# Backplane.net
KiCad netlist of a schematic drawn in EAGLE
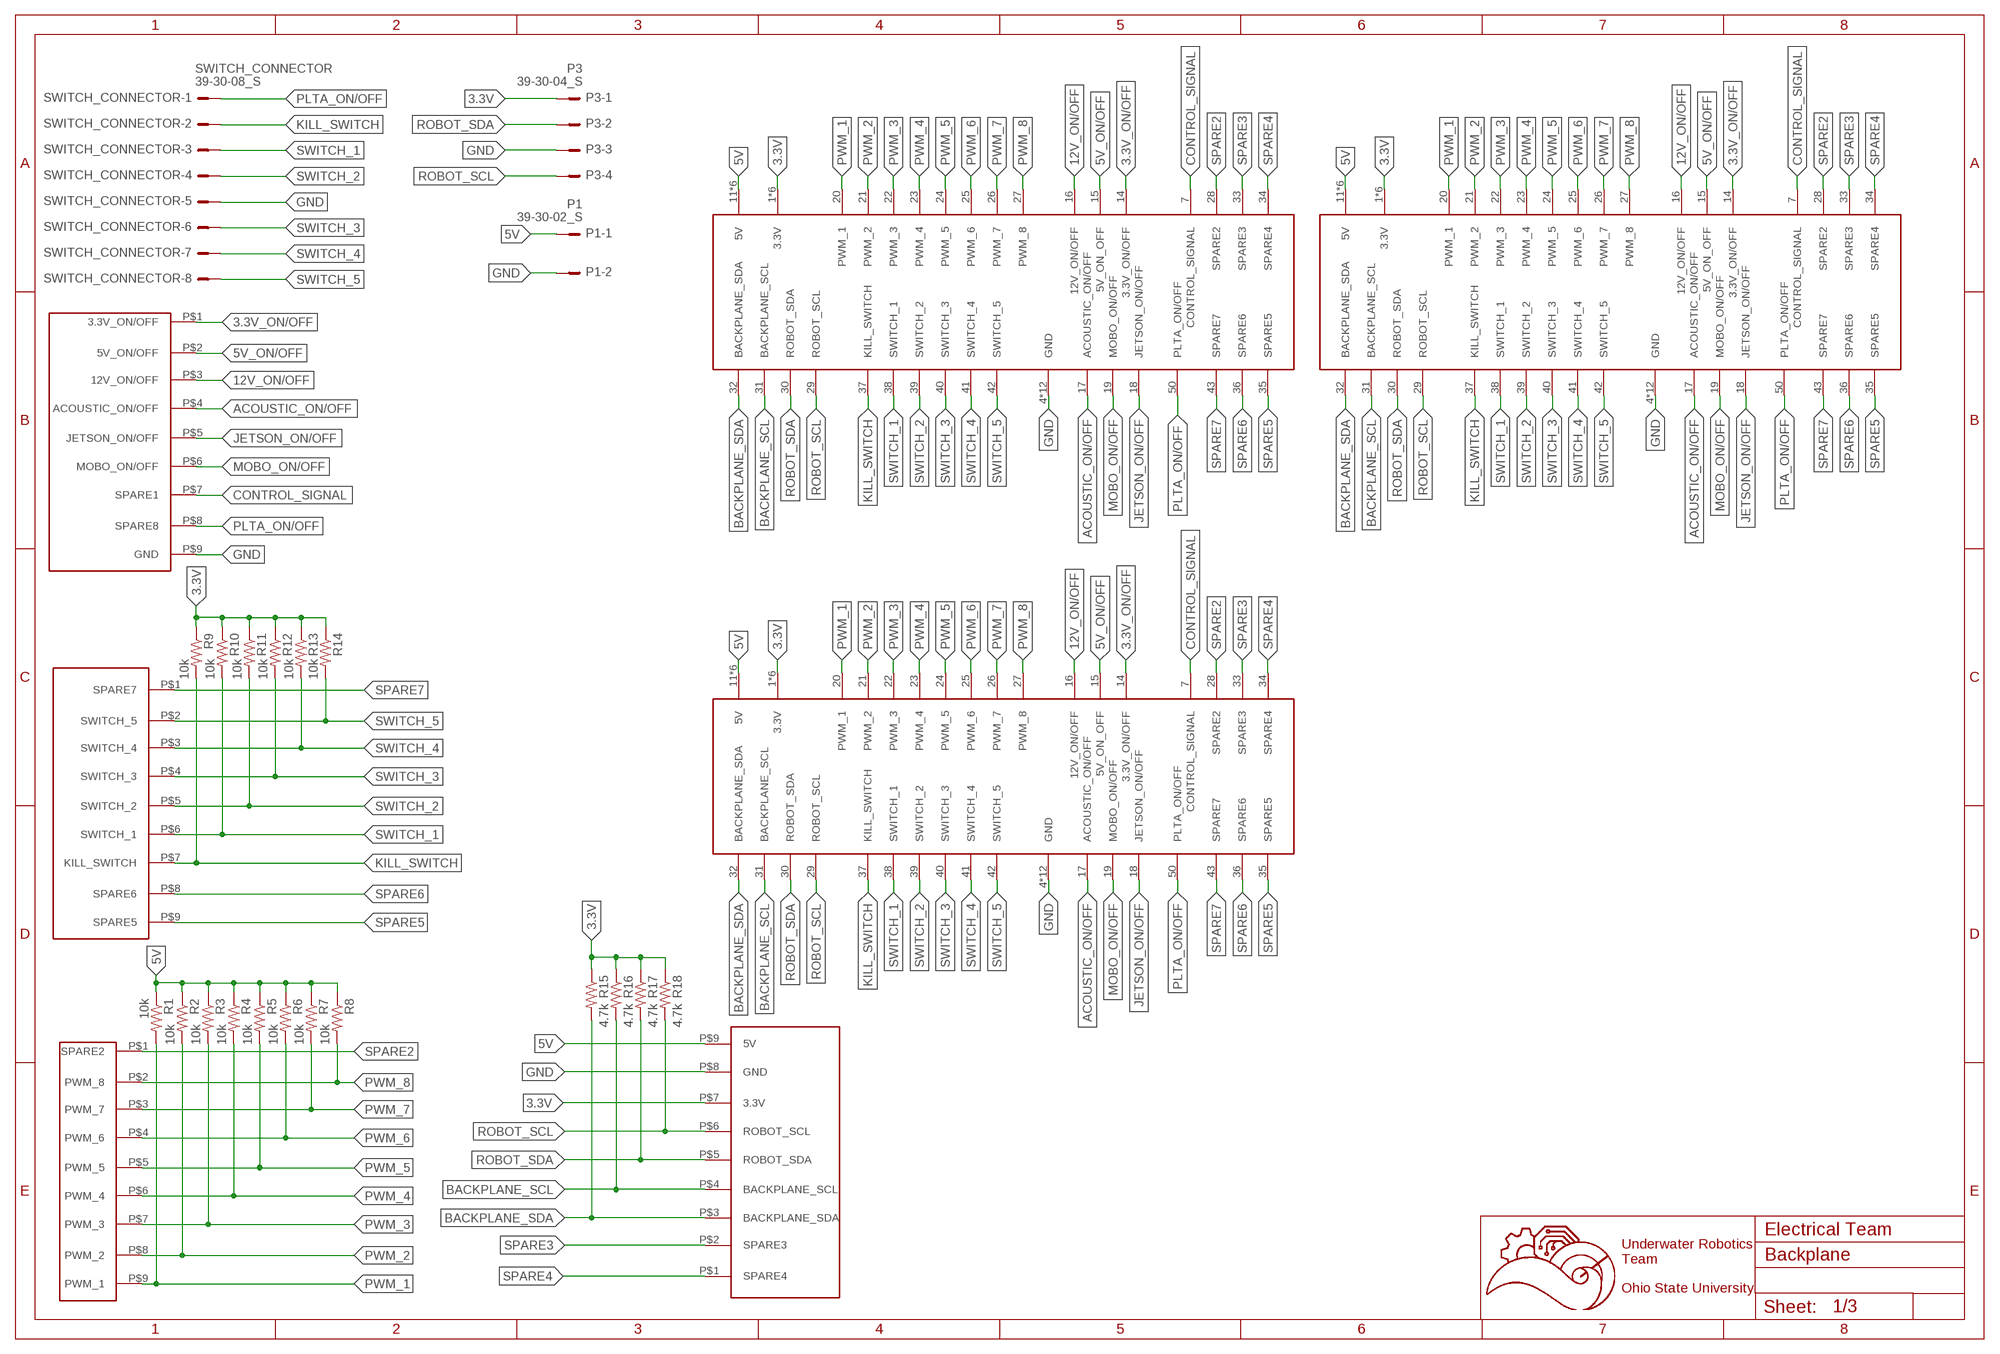
[diagram p0: schematic, sheet 1]
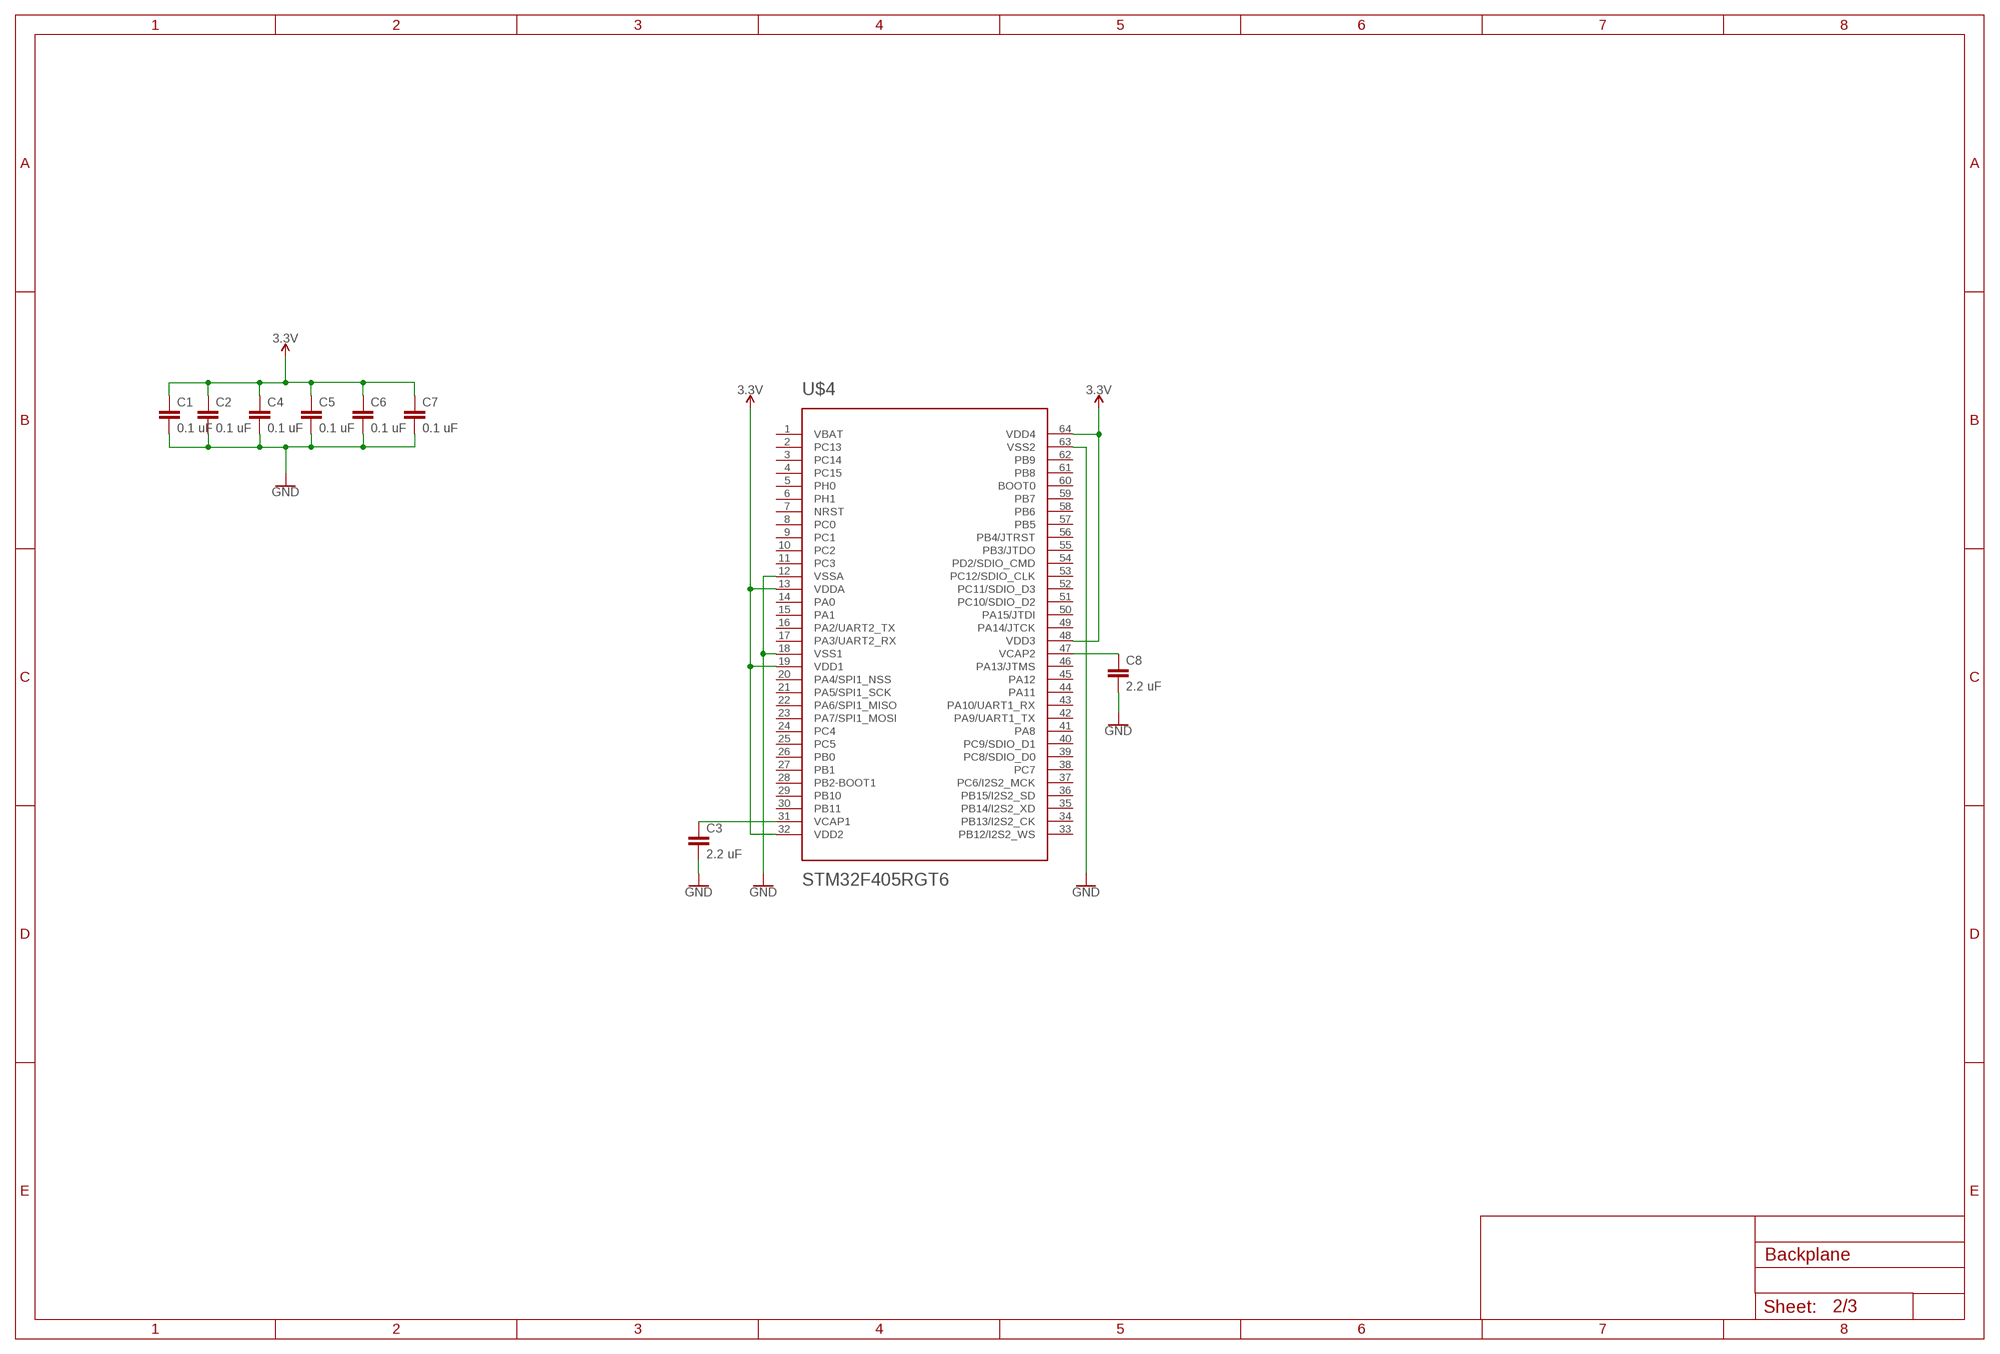
[diagram p1: schematic, sheet 2]

(export (version "E")
  (design (tool "Eeschema 10.0.6"))
  (components
    (comp (ref "C1")
      (value "0.1 uF")
      (footprint "eagle-import:C0603")
      (libsource (lib "eagle-import") (part "C-EUC0603"))
    )
    (comp (ref "C2")
      (value "0.1 uF")
      (footprint "eagle-import:C0603")
      (libsource (lib "eagle-import") (part "C-EUC0603"))
    )
    (comp (ref "C3")
      (value "2.2 uF")
      (footprint "eagle-import:C0603")
      (libsource (lib "eagle-import") (part "C-EUC0603"))
    )
    (comp (ref "C4")
      (value "0.1 uF")
      (footprint "eagle-import:C0603")
      (libsource (lib "eagle-import") (part "C-EUC0603"))
    )
    (comp (ref "C5")
      (value "0.1 uF")
      (footprint "eagle-import:C0603")
      (libsource (lib "eagle-import") (part "C-EUC0603"))
    )
    (comp (ref "C6")
      (value "0.1 uF")
      (footprint "eagle-import:C0603")
      (libsource (lib "eagle-import") (part "C-EUC0603"))
    )
    (comp (ref "C7")
      (value "0.1 uF")
      (footprint "eagle-import:C0603")
      (libsource (lib "eagle-import") (part "C-EUC0603"))
    )
    (comp (ref "C8")
      (value "2.2 uF")
      (footprint "eagle-import:C0603")
      (libsource (lib "eagle-import") (part "C-EUC0603"))
    )
    (comp (ref "U$4")
      (value "STM32F405RGT6")
      (footprint "eagle-import:TQFP64")
      (libsource (lib "eagle-import") (part "STM32F405RG"))
    )
    (comp (ref "P1")
      (value "39-30-02_S")
      (footprint "eagle-import:39-30-_02_")
      (libsource (lib "eagle-import") (part "39-30-?02?_S"))
    )
    (comp (ref "P3")
      (value "39-30-04_S")
      (footprint "eagle-import:39-30-_04_")
      (libsource (lib "eagle-import") (part "39-30-?04?_S"))
    )
    (comp (ref "R1")
      (value "10k")
      (footprint "eagle-import:R0603")
      (libsource (lib "eagle-import") (part "R-US_R0603"))
    )
    (comp (ref "R2")
      (value "10k")
      (footprint "eagle-import:R0603")
      (libsource (lib "eagle-import") (part "R-US_R0603"))
    )
    (comp (ref "R3")
      (value "10k")
      (footprint "eagle-import:R0603")
      (libsource (lib "eagle-import") (part "R-US_R0603"))
    )
    (comp (ref "R4")
      (value "10k")
      (footprint "eagle-import:R0603")
      (libsource (lib "eagle-import") (part "R-US_R0603"))
    )
    (comp (ref "R5")
      (value "10k")
      (footprint "eagle-import:R0603")
      (libsource (lib "eagle-import") (part "R-US_R0603"))
    )
    (comp (ref "R6")
      (value "10k")
      (footprint "eagle-import:R0603")
      (libsource (lib "eagle-import") (part "R-US_R0603"))
    )
    (comp (ref "R7")
      (value "10k")
      (footprint "eagle-import:R0603")
      (libsource (lib "eagle-import") (part "R-US_R0603"))
    )
    (comp (ref "R8")
      (value "10k")
      (footprint "eagle-import:R0603")
      (libsource (lib "eagle-import") (part "R-US_R0603"))
    )
    (comp (ref "R9")
      (value "10k")
      (footprint "eagle-import:R0603")
      (libsource (lib "eagle-import") (part "R-US_R0603"))
    )
    (comp (ref "R10")
      (value "10k")
      (footprint "eagle-import:R0603")
      (libsource (lib "eagle-import") (part "R-US_R0603"))
    )
    (comp (ref "R11")
      (value "10k")
      (footprint "eagle-import:R0603")
      (libsource (lib "eagle-import") (part "R-US_R0603"))
    )
    (comp (ref "R12")
      (value "10k")
      (footprint "eagle-import:R0603")
      (libsource (lib "eagle-import") (part "R-US_R0603"))
    )
    (comp (ref "R13")
      (value "10k")
      (footprint "eagle-import:R0603")
      (libsource (lib "eagle-import") (part "R-US_R0603"))
    )
    (comp (ref "R14")
      (value "10k")
      (footprint "eagle-import:R0603")
      (libsource (lib "eagle-import") (part "R-US_R0603"))
    )
    (comp (ref "R15")
      (value "4.7k")
      (footprint "eagle-import:R0603")
      (libsource (lib "eagle-import") (part "R-US_R0603"))
    )
    (comp (ref "R16")
      (value "4.7k")
      (footprint "eagle-import:R0603")
      (libsource (lib "eagle-import") (part "R-US_R0603"))
    )
    (comp (ref "R17")
      (value "4.7k")
      (footprint "eagle-import:R0603")
      (libsource (lib "eagle-import") (part "R-US_R0603"))
    )
    (comp (ref "R18")
      (value "4.7k")
      (footprint "eagle-import:R0603")
      (libsource (lib "eagle-import") (part "R-US_R0603"))
    )
    (comp (ref "SWITCH_CONNECTOR")
      (value "39-30-08_S")
      (footprint "eagle-import:39-30-_08_")
      (libsource (lib "eagle-import") (part "39-30-?08?_S"))
    )
    (comp (ref "U$1")
      (value "5530843-FEMALE")
      (footprint "eagle-import:5530843-6-BACKPLANEMATE")
      (libsource (lib "eagle-import") (part "5530843-FEMALE"))
    )
    (comp (ref "U$2")
      (value "5530843-FEMALE")
      (footprint "eagle-import:5530843-6-BACKPLANEMATE")
      (libsource (lib "eagle-import") (part "5530843-FEMALE"))
    )
    (comp (ref "U$3")
      (value "5530843-FEMALE")
      (footprint "eagle-import:5530843-6-BACKPLANEMATE")
      (libsource (lib "eagle-import") (part "5530843-FEMALE"))
    )
    (comp (ref "U$5")
      (value "929870-01-09_1")
      (footprint "eagle-import:929852-01-09_1ROW")
      (libsource (lib "eagle-import") (part "929870-01-09_1"))
    )
    (comp (ref "U$6")
      (value "929870-01-09_2")
      (footprint "eagle-import:929852-01-09_1ROW")
      (libsource (lib "eagle-import") (part "929870-01-09_2"))
    )
    (comp (ref "U$7")
      (value "929870-01-09_3")
      (footprint "eagle-import:929852-01-09_1ROW")
      (libsource (lib "eagle-import") (part "929870-01-09_3"))
    )
    (comp (ref "U$8")
      (value "929870-01-09_4")
      (footprint "eagle-import:929852-01-09_1ROW")
      (libsource (lib "eagle-import") (part "929870-01-09_4"))
    )
  )
  (nets
    (net (code "1") (name "3.3V") (class "Default")
      (node (ref "C1") (pin "1") (pinfunction "1_1") (pintype "passive"))
      (node (ref "C2") (pin "1") (pinfunction "1_1") (pintype "passive"))
      (node (ref "C4") (pin "1") (pinfunction "1_1") (pintype "passive"))
      (node (ref "C5") (pin "1") (pinfunction "1_1") (pintype "passive"))
      (node (ref "C6") (pin "1") (pinfunction "1_1") (pintype "passive"))
      (node (ref "C7") (pin "1") (pinfunction "1_1") (pintype "passive"))
      (node (ref "P3") (pin "1") (pinfunction "P_1") (pintype "passive"))
      (node (ref "R10") (pin "1") (pinfunction "1_1") (pintype "passive"))
      (node (ref "R11") (pin "1") (pinfunction "1_1") (pintype "passive"))
      (node (ref "R12") (pin "1") (pinfunction "1_1") (pintype "passive"))
      (node (ref "R13") (pin "1") (pinfunction "1_1") (pintype "passive"))
      (node (ref "R14") (pin "1") (pinfunction "1_1") (pintype "passive"))
      (node (ref "R15") (pin "1") (pinfunction "1_1") (pintype "passive"))
      (node (ref "R16") (pin "1") (pinfunction "1_1") (pintype "passive"))
      (node (ref "R17") (pin "1") (pinfunction "1_1") (pintype "passive"))
      (node (ref "R18") (pin "1") (pinfunction "1_1") (pintype "passive"))
      (node (ref "R9") (pin "1") (pinfunction "1_1") (pintype "passive"))
      (node (ref "U$1") (pin "1") (pinfunction "3.3V_1") (pintype "bidirectional"))
      (node (ref "U$1") (pin "2") (pinfunction "3.3V_2") (pintype "bidirectional"))
      (node (ref "U$1") (pin "3") (pinfunction "3.3V_3") (pintype "bidirectional"))
      (node (ref "U$1") (pin "54") (pinfunction "3.3V_54") (pintype "bidirectional"))
      (node (ref "U$1") (pin "55") (pinfunction "3.3V_55") (pintype "bidirectional"))
      (node (ref "U$1") (pin "56") (pinfunction "3.3V_56") (pintype "bidirectional"))
      (node (ref "U$2") (pin "1") (pinfunction "3.3V_1") (pintype "bidirectional"))
      (node (ref "U$2") (pin "2") (pinfunction "3.3V_2") (pintype "bidirectional"))
      (node (ref "U$2") (pin "3") (pinfunction "3.3V_3") (pintype "bidirectional"))
      (node (ref "U$2") (pin "54") (pinfunction "3.3V_54") (pintype "bidirectional"))
      (node (ref "U$2") (pin "55") (pinfunction "3.3V_55") (pintype "bidirectional"))
      (node (ref "U$2") (pin "56") (pinfunction "3.3V_56") (pintype "bidirectional"))
      (node (ref "U$3") (pin "1") (pinfunction "3.3V_1") (pintype "bidirectional"))
      (node (ref "U$3") (pin "2") (pinfunction "3.3V_2") (pintype "bidirectional"))
      (node (ref "U$3") (pin "3") (pinfunction "3.3V_3") (pintype "bidirectional"))
      (node (ref "U$3") (pin "54") (pinfunction "3.3V_54") (pintype "bidirectional"))
      (node (ref "U$3") (pin "55") (pinfunction "3.3V_55") (pintype "bidirectional"))
      (node (ref "U$3") (pin "56") (pinfunction "3.3V_56") (pintype "bidirectional"))
      (node (ref "U$4") (pin "13") (pinfunction "VDDA_13") (pintype "bidirectional"))
      (node (ref "U$4") (pin "19") (pinfunction "VDD1_19") (pintype "bidirectional"))
      (node (ref "U$4") (pin "32") (pinfunction "VDD2_32") (pintype "bidirectional"))
      (node (ref "U$4") (pin "48") (pinfunction "VDD3_48") (pintype "bidirectional"))
      (node (ref "U$4") (pin "64") (pinfunction "VDD4_64") (pintype "bidirectional"))
      (node (ref "U$8") (pin "P$7") (pinfunction "3.3V_P$7") (pintype "bidirectional"))
    )
    (net (code "2") (name "3.3V_ON{slash}OFF") (class "Default")
      (node (ref "U$1") (pin "14") (pinfunction "3.3V_ON/OFF_14") (pintype "bidirectional"))
      (node (ref "U$2") (pin "14") (pinfunction "3.3V_ON/OFF_14") (pintype "bidirectional"))
      (node (ref "U$3") (pin "14") (pinfunction "3.3V_ON/OFF_14") (pintype "bidirectional"))
      (node (ref "U$7") (pin "P$1") (pinfunction "3.3V_ON/OFF_P$1") (pintype "bidirectional"))
    )
    (net (code "3") (name "5V") (class "Default")
      (node (ref "P1") (pin "1") (pinfunction "P_1") (pintype "passive"))
      (node (ref "R1") (pin "1") (pinfunction "1_1") (pintype "passive"))
      (node (ref "R2") (pin "1") (pinfunction "1_1") (pintype "passive"))
      (node (ref "R3") (pin "1") (pinfunction "1_1") (pintype "passive"))
      (node (ref "R4") (pin "1") (pinfunction "1_1") (pintype "passive"))
      (node (ref "R5") (pin "1") (pinfunction "1_1") (pintype "passive"))
      (node (ref "R6") (pin "1") (pinfunction "1_1") (pintype "passive"))
      (node (ref "R7") (pin "1") (pinfunction "1_1") (pintype "passive"))
      (node (ref "R8") (pin "1") (pinfunction "1_1") (pintype "passive"))
      (node (ref "U$1") (pin "11") (pinfunction "5V_11") (pintype "bidirectional"))
      (node (ref "U$1") (pin "12") (pinfunction "5V_12") (pintype "bidirectional"))
      (node (ref "U$1") (pin "13") (pinfunction "5V_13") (pintype "bidirectional"))
      (node (ref "U$1") (pin "44") (pinfunction "5V_44") (pintype "bidirectional"))
      (node (ref "U$1") (pin "45") (pinfunction "5V_45") (pintype "bidirectional"))
      (node (ref "U$1") (pin "46") (pinfunction "5V_46") (pintype "bidirectional"))
      (node (ref "U$2") (pin "11") (pinfunction "5V_11") (pintype "bidirectional"))
      (node (ref "U$2") (pin "12") (pinfunction "5V_12") (pintype "bidirectional"))
      (node (ref "U$2") (pin "13") (pinfunction "5V_13") (pintype "bidirectional"))
      (node (ref "U$2") (pin "44") (pinfunction "5V_44") (pintype "bidirectional"))
      (node (ref "U$2") (pin "45") (pinfunction "5V_45") (pintype "bidirectional"))
      (node (ref "U$2") (pin "46") (pinfunction "5V_46") (pintype "bidirectional"))
      (node (ref "U$3") (pin "11") (pinfunction "5V_11") (pintype "bidirectional"))
      (node (ref "U$3") (pin "12") (pinfunction "5V_12") (pintype "bidirectional"))
      (node (ref "U$3") (pin "13") (pinfunction "5V_13") (pintype "bidirectional"))
      (node (ref "U$3") (pin "44") (pinfunction "5V_44") (pintype "bidirectional"))
      (node (ref "U$3") (pin "45") (pinfunction "5V_45") (pintype "bidirectional"))
      (node (ref "U$3") (pin "46") (pinfunction "5V_46") (pintype "bidirectional"))
      (node (ref "U$8") (pin "P$9") (pinfunction "5V_P$9") (pintype "bidirectional"))
    )
    (net (code "4") (name "5V_ON{slash}OFF") (class "Default")
      (node (ref "U$1") (pin "15") (pinfunction "5V_ON_OFF_15") (pintype "bidirectional"))
      (node (ref "U$2") (pin "15") (pinfunction "5V_ON_OFF_15") (pintype "bidirectional"))
      (node (ref "U$3") (pin "15") (pinfunction "5V_ON_OFF_15") (pintype "bidirectional"))
      (node (ref "U$7") (pin "P$2") (pinfunction "5V_ON/OFF_P$2") (pintype "bidirectional"))
    )
    (net (code "5") (name "12V_ON{slash}OFF") (class "Default")
      (node (ref "U$1") (pin "16") (pinfunction "12V_ON/OFF_16") (pintype "bidirectional"))
      (node (ref "U$2") (pin "16") (pinfunction "12V_ON/OFF_16") (pintype "bidirectional"))
      (node (ref "U$3") (pin "16") (pinfunction "12V_ON/OFF_16") (pintype "bidirectional"))
      (node (ref "U$7") (pin "P$3") (pinfunction "12V_ON/OFF_P$3") (pintype "bidirectional"))
    )
    (net (code "6") (name "ACOUSTIC_ON{slash}OFF") (class "Default")
      (node (ref "U$1") (pin "17") (pinfunction "ACOUSTIC_ON/OFF_17") (pintype "bidirectional"))
      (node (ref "U$2") (pin "17") (pinfunction "ACOUSTIC_ON/OFF_17") (pintype "bidirectional"))
      (node (ref "U$3") (pin "17") (pinfunction "ACOUSTIC_ON/OFF_17") (pintype "bidirectional"))
      (node (ref "U$7") (pin "P$4") (pinfunction "ACOUSTIC_ON/OFF_P$4") (pintype "bidirectional"))
    )
    (net (code "7") (name "BACKPLANE_SCL") (class "Default")
      (node (ref "R16") (pin "2") (pinfunction "2_2") (pintype "passive"))
      (node (ref "U$1") (pin "31") (pinfunction "BACKPLANE_SCL_31") (pintype "bidirectional"))
      (node (ref "U$2") (pin "31") (pinfunction "BACKPLANE_SCL_31") (pintype "bidirectional"))
      (node (ref "U$3") (pin "31") (pinfunction "BACKPLANE_SCL_31") (pintype "bidirectional"))
      (node (ref "U$8") (pin "P$4") (pinfunction "BACKPLANE_SCL_P$4") (pintype "bidirectional"))
    )
    (net (code "8") (name "BACKPLANE_SDA") (class "Default")
      (node (ref "R15") (pin "2") (pinfunction "2_2") (pintype "passive"))
      (node (ref "U$1") (pin "32") (pinfunction "BACKPLANE_SDA_32") (pintype "bidirectional"))
      (node (ref "U$2") (pin "32") (pinfunction "BACKPLANE_SDA_32") (pintype "bidirectional"))
      (node (ref "U$3") (pin "32") (pinfunction "BACKPLANE_SDA_32") (pintype "bidirectional"))
      (node (ref "U$8") (pin "P$3") (pinfunction "BACKPLANE_SDA_P$3") (pintype "bidirectional"))
    )
    (net (code "9") (name "CONTROL_SIGNAL") (class "Default")
      (node (ref "U$1") (pin "7") (pinfunction "CONTROL_SIGNAL_7") (pintype "bidirectional"))
      (node (ref "U$2") (pin "7") (pinfunction "CONTROL_SIGNAL_7") (pintype "bidirectional"))
      (node (ref "U$3") (pin "7") (pinfunction "CONTROL_SIGNAL_7") (pintype "bidirectional"))
      (node (ref "U$7") (pin "P$7") (pinfunction "SPARE1_P$7") (pintype "bidirectional"))
    )
    (net (code "10") (name "GND") (class "Default")
      (node (ref "C1") (pin "2") (pinfunction "2_2") (pintype "passive"))
      (node (ref "C2") (pin "2") (pinfunction "2_2") (pintype "passive"))
      (node (ref "C3") (pin "2") (pinfunction "2_2") (pintype "passive"))
      (node (ref "C4") (pin "2") (pinfunction "2_2") (pintype "passive"))
      (node (ref "C5") (pin "2") (pinfunction "2_2") (pintype "passive"))
      (node (ref "C6") (pin "2") (pinfunction "2_2") (pintype "passive"))
      (node (ref "C7") (pin "2") (pinfunction "2_2") (pintype "passive"))
      (node (ref "C8") (pin "2") (pinfunction "2_2") (pintype "passive"))
      (node (ref "P1") (pin "2") (pinfunction "P_2") (pintype "passive"))
      (node (ref "P3") (pin "3") (pinfunction "P_3") (pintype "passive"))
      (node (ref "SWITCH_CONNECTOR") (pin "5") (pinfunction "P_5") (pintype "passive"))
      (node (ref "U$1") (pin "10") (pinfunction "GND_10") (pintype "bidirectional"))
      (node (ref "U$1") (pin "4") (pinfunction "GND_4") (pintype "bidirectional"))
      (node (ref "U$1") (pin "47") (pinfunction "GND_47") (pintype "bidirectional"))
      (node (ref "U$1") (pin "48") (pinfunction "GND_48") (pintype "bidirectional"))
      (node (ref "U$1") (pin "49") (pinfunction "GND_49") (pintype "bidirectional"))
      (node (ref "U$1") (pin "5") (pinfunction "GND_5") (pintype "bidirectional"))
      (node (ref "U$1") (pin "51") (pinfunction "GND_51") (pintype "bidirectional"))
      (node (ref "U$1") (pin "52") (pinfunction "GND_52") (pintype "bidirectional"))
      (node (ref "U$1") (pin "53") (pinfunction "GND_53") (pintype "bidirectional"))
      (node (ref "U$1") (pin "6") (pinfunction "GND_6") (pintype "bidirectional"))
      (node (ref "U$1") (pin "8") (pinfunction "GND_8") (pintype "bidirectional"))
      (node (ref "U$1") (pin "9") (pinfunction "GND_9") (pintype "bidirectional"))
      (node (ref "U$2") (pin "10") (pinfunction "GND_10") (pintype "bidirectional"))
      (node (ref "U$2") (pin "4") (pinfunction "GND_4") (pintype "bidirectional"))
      (node (ref "U$2") (pin "47") (pinfunction "GND_47") (pintype "bidirectional"))
      (node (ref "U$2") (pin "48") (pinfunction "GND_48") (pintype "bidirectional"))
      (node (ref "U$2") (pin "49") (pinfunction "GND_49") (pintype "bidirectional"))
      (node (ref "U$2") (pin "5") (pinfunction "GND_5") (pintype "bidirectional"))
      (node (ref "U$2") (pin "51") (pinfunction "GND_51") (pintype "bidirectional"))
      (node (ref "U$2") (pin "52") (pinfunction "GND_52") (pintype "bidirectional"))
      (node (ref "U$2") (pin "53") (pinfunction "GND_53") (pintype "bidirectional"))
      (node (ref "U$2") (pin "6") (pinfunction "GND_6") (pintype "bidirectional"))
      (node (ref "U$2") (pin "8") (pinfunction "GND_8") (pintype "bidirectional"))
      (node (ref "U$2") (pin "9") (pinfunction "GND_9") (pintype "bidirectional"))
      (node (ref "U$3") (pin "10") (pinfunction "GND_10") (pintype "bidirectional"))
      (node (ref "U$3") (pin "4") (pinfunction "GND_4") (pintype "bidirectional"))
      (node (ref "U$3") (pin "47") (pinfunction "GND_47") (pintype "bidirectional"))
      (node (ref "U$3") (pin "48") (pinfunction "GND_48") (pintype "bidirectional"))
      (node (ref "U$3") (pin "49") (pinfunction "GND_49") (pintype "bidirectional"))
      (node (ref "U$3") (pin "5") (pinfunction "GND_5") (pintype "bidirectional"))
      (node (ref "U$3") (pin "51") (pinfunction "GND_51") (pintype "bidirectional"))
      (node (ref "U$3") (pin "52") (pinfunction "GND_52") (pintype "bidirectional"))
      (node (ref "U$3") (pin "53") (pinfunction "GND_53") (pintype "bidirectional"))
      (node (ref "U$3") (pin "6") (pinfunction "GND_6") (pintype "bidirectional"))
      (node (ref "U$3") (pin "8") (pinfunction "GND_8") (pintype "bidirectional"))
      (node (ref "U$3") (pin "9") (pinfunction "GND_9") (pintype "bidirectional"))
      (node (ref "U$4") (pin "12") (pinfunction "VSSA_12") (pintype "bidirectional"))
      (node (ref "U$4") (pin "18") (pinfunction "VSS1_18") (pintype "bidirectional"))
      (node (ref "U$4") (pin "63") (pinfunction "VSS2_63") (pintype "bidirectional"))
      (node (ref "U$7") (pin "P$9") (pinfunction "GND_P$9") (pintype "bidirectional"))
      (node (ref "U$8") (pin "P$8") (pinfunction "GND_P$8") (pintype "bidirectional"))
    )
    (net (code "11") (name "JETSON_ON{slash}OFF") (class "Default")
      (node (ref "U$1") (pin "18") (pinfunction "JETSON_ON/OFF_18") (pintype "bidirectional"))
      (node (ref "U$2") (pin "18") (pinfunction "JETSON_ON/OFF_18") (pintype "bidirectional"))
      (node (ref "U$3") (pin "18") (pinfunction "JETSON_ON/OFF_18") (pintype "bidirectional"))
      (node (ref "U$7") (pin "P$5") (pinfunction "JETSON_ON/OFF_P$5") (pintype "bidirectional"))
    )
    (net (code "12") (name "KILL_SWITCH") (class "Default")
      (node (ref "R9") (pin "2") (pinfunction "2_2") (pintype "passive"))
      (node (ref "SWITCH_CONNECTOR") (pin "2") (pinfunction "P_2") (pintype "passive"))
      (node (ref "U$1") (pin "37") (pinfunction "KILL_SWITCH_37") (pintype "output"))
      (node (ref "U$2") (pin "37") (pinfunction "KILL_SWITCH_37") (pintype "output"))
      (node (ref "U$3") (pin "37") (pinfunction "KILL_SWITCH_37") (pintype "output"))
      (node (ref "U$5") (pin "P$7") (pinfunction "KILL_SWITCH_P$7") (pintype "bidirectional"))
    )
    (net (code "13") (name "MOBO_ON{slash}OFF") (class "Default")
      (node (ref "U$1") (pin "19") (pinfunction "MOBO_ON/OFF_19") (pintype "bidirectional"))
      (node (ref "U$2") (pin "19") (pinfunction "MOBO_ON/OFF_19") (pintype "bidirectional"))
      (node (ref "U$3") (pin "19") (pinfunction "MOBO_ON/OFF_19") (pintype "bidirectional"))
      (node (ref "U$7") (pin "P$6") (pinfunction "MOBO_ON/OFF_P$6") (pintype "bidirectional"))
    )
    (net (code "14") (name "Net-(U$4-VCAP1)") (class "Default")
      (node (ref "C3") (pin "1") (pinfunction "1_1") (pintype "passive"))
      (node (ref "U$4") (pin "31") (pinfunction "VCAP1_31") (pintype "bidirectional"))
    )
    (net (code "15") (name "Net-(U$4-VCAP2)") (class "Default")
      (node (ref "C8") (pin "1") (pinfunction "1_1") (pintype "passive"))
      (node (ref "U$4") (pin "47") (pinfunction "VCAP2_47") (pintype "bidirectional"))
    )
    (net (code "16") (name "PLTA_ON{slash}OFF") (class "Default")
      (node (ref "SWITCH_CONNECTOR") (pin "1") (pinfunction "P_1") (pintype "passive"))
      (node (ref "U$1") (pin "50") (pinfunction "PLTA_ON/OFF_50") (pintype "bidirectional"))
      (node (ref "U$2") (pin "50") (pinfunction "PLTA_ON/OFF_50") (pintype "bidirectional"))
      (node (ref "U$3") (pin "50") (pinfunction "PLTA_ON/OFF_50") (pintype "bidirectional"))
      (node (ref "U$7") (pin "P$8") (pinfunction "SPARE8_P$8") (pintype "bidirectional"))
    )
    (net (code "17") (name "PWM_1") (class "Default")
      (node (ref "R1") (pin "2") (pinfunction "2_2") (pintype "passive"))
      (node (ref "U$1") (pin "20") (pinfunction "PWM_1_20") (pintype "bidirectional"))
      (node (ref "U$2") (pin "20") (pinfunction "PWM_1_20") (pintype "bidirectional"))
      (node (ref "U$3") (pin "20") (pinfunction "PWM_1_20") (pintype "bidirectional"))
      (node (ref "U$6") (pin "P$9") (pinfunction "PWM_1_P$9") (pintype "bidirectional"))
    )
    (net (code "18") (name "PWM_2") (class "Default")
      (node (ref "R2") (pin "2") (pinfunction "2_2") (pintype "passive"))
      (node (ref "U$1") (pin "21") (pinfunction "PWM_2_21") (pintype "bidirectional"))
      (node (ref "U$2") (pin "21") (pinfunction "PWM_2_21") (pintype "bidirectional"))
      (node (ref "U$3") (pin "21") (pinfunction "PWM_2_21") (pintype "bidirectional"))
      (node (ref "U$6") (pin "P$8") (pinfunction "PWM_2_P$8") (pintype "bidirectional"))
    )
    (net (code "19") (name "PWM_3") (class "Default")
      (node (ref "R3") (pin "2") (pinfunction "2_2") (pintype "passive"))
      (node (ref "U$1") (pin "22") (pinfunction "PWM_3_22") (pintype "bidirectional"))
      (node (ref "U$2") (pin "22") (pinfunction "PWM_3_22") (pintype "bidirectional"))
      (node (ref "U$3") (pin "22") (pinfunction "PWM_3_22") (pintype "bidirectional"))
      (node (ref "U$6") (pin "P$7") (pinfunction "PWM_3_P$7") (pintype "bidirectional"))
    )
    (net (code "20") (name "PWM_4") (class "Default")
      (node (ref "R4") (pin "2") (pinfunction "2_2") (pintype "passive"))
      (node (ref "U$1") (pin "23") (pinfunction "PWM_4_23") (pintype "bidirectional"))
      (node (ref "U$2") (pin "23") (pinfunction "PWM_4_23") (pintype "bidirectional"))
      (node (ref "U$3") (pin "23") (pinfunction "PWM_4_23") (pintype "bidirectional"))
      (node (ref "U$6") (pin "P$6") (pinfunction "PWM_4_P$6") (pintype "bidirectional"))
    )
    (net (code "21") (name "PWM_5") (class "Default")
      (node (ref "R5") (pin "2") (pinfunction "2_2") (pintype "passive"))
      (node (ref "U$1") (pin "24") (pinfunction "PWM_5_24") (pintype "bidirectional"))
      (node (ref "U$2") (pin "24") (pinfunction "PWM_5_24") (pintype "bidirectional"))
      (node (ref "U$3") (pin "24") (pinfunction "PWM_5_24") (pintype "bidirectional"))
      (node (ref "U$6") (pin "P$5") (pinfunction "PWM_5_P$5") (pintype "bidirectional"))
    )
    (net (code "22") (name "PWM_6") (class "Default")
      (node (ref "R6") (pin "2") (pinfunction "2_2") (pintype "passive"))
      (node (ref "U$1") (pin "25") (pinfunction "PWM_6_25") (pintype "bidirectional"))
      (node (ref "U$2") (pin "25") (pinfunction "PWM_6_25") (pintype "bidirectional"))
      (node (ref "U$3") (pin "25") (pinfunction "PWM_6_25") (pintype "bidirectional"))
      (node (ref "U$6") (pin "P$4") (pinfunction "PWM_6_P$4") (pintype "bidirectional"))
    )
    (net (code "23") (name "PWM_7") (class "Default")
      (node (ref "R7") (pin "2") (pinfunction "2_2") (pintype "passive"))
      (node (ref "U$1") (pin "26") (pinfunction "PWM_7_26") (pintype "bidirectional"))
      (node (ref "U$2") (pin "26") (pinfunction "PWM_7_26") (pintype "bidirectional"))
      (node (ref "U$3") (pin "26") (pinfunction "PWM_7_26") (pintype "bidirectional"))
      (node (ref "U$6") (pin "P$3") (pinfunction "PWM_7_P$3") (pintype "bidirectional"))
    )
    (net (code "24") (name "PWM_8") (class "Default")
      (node (ref "R8") (pin "2") (pinfunction "2_2") (pintype "passive"))
      (node (ref "U$1") (pin "27") (pinfunction "PWM_8_27") (pintype "bidirectional"))
      (node (ref "U$2") (pin "27") (pinfunction "PWM_8_27") (pintype "bidirectional"))
      (node (ref "U$3") (pin "27") (pinfunction "PWM_8_27") (pintype "bidirectional"))
      (node (ref "U$6") (pin "P$2") (pinfunction "PWM_8_P$2") (pintype "bidirectional"))
    )
    (net (code "25") (name "ROBOT_SCL") (class "Default")
      (node (ref "P3") (pin "4") (pinfunction "P_4") (pintype "passive"))
      (node (ref "R18") (pin "2") (pinfunction "2_2") (pintype "passive"))
      (node (ref "U$1") (pin "29") (pinfunction "ROBOT_SCL_29") (pintype "bidirectional"))
      (node (ref "U$2") (pin "29") (pinfunction "ROBOT_SCL_29") (pintype "bidirectional"))
      (node (ref "U$3") (pin "29") (pinfunction "ROBOT_SCL_29") (pintype "bidirectional"))
      (node (ref "U$8") (pin "P$6") (pinfunction "ROBOT_SCL_P$6") (pintype "bidirectional"))
    )
    (net (code "26") (name "ROBOT_SDA") (class "Default")
      (node (ref "P3") (pin "2") (pinfunction "P_2") (pintype "passive"))
      (node (ref "R17") (pin "2") (pinfunction "2_2") (pintype "passive"))
      (node (ref "U$1") (pin "30") (pinfunction "ROBOT_SDA_30") (pintype "bidirectional"))
      (node (ref "U$2") (pin "30") (pinfunction "ROBOT_SDA_30") (pintype "bidirectional"))
      (node (ref "U$3") (pin "30") (pinfunction "ROBOT_SDA_30") (pintype "bidirectional"))
      (node (ref "U$8") (pin "P$5") (pinfunction "ROBOT_SDA_P$5") (pintype "bidirectional"))
    )
    (net (code "27") (name "SPARE2") (class "Default")
      (node (ref "U$1") (pin "28") (pinfunction "SPARE2_28") (pintype "bidirectional"))
      (node (ref "U$2") (pin "28") (pinfunction "SPARE2_28") (pintype "bidirectional"))
      (node (ref "U$3") (pin "28") (pinfunction "SPARE2_28") (pintype "bidirectional"))
      (node (ref "U$6") (pin "P$1") (pinfunction "SPARE2_P$1") (pintype "bidirectional"))
    )
    (net (code "28") (name "SPARE3") (class "Default")
      (node (ref "U$1") (pin "33") (pinfunction "SPARE3_33") (pintype "bidirectional"))
      (node (ref "U$2") (pin "33") (pinfunction "SPARE3_33") (pintype "bidirectional"))
      (node (ref "U$3") (pin "33") (pinfunction "SPARE3_33") (pintype "bidirectional"))
      (node (ref "U$8") (pin "P$2") (pinfunction "SPARE3_P$2") (pintype "bidirectional"))
    )
    (net (code "29") (name "SPARE4") (class "Default")
      (node (ref "U$1") (pin "34") (pinfunction "SPARE4_34") (pintype "bidirectional"))
      (node (ref "U$2") (pin "34") (pinfunction "SPARE4_34") (pintype "bidirectional"))
      (node (ref "U$3") (pin "34") (pinfunction "SPARE4_34") (pintype "bidirectional"))
      (node (ref "U$8") (pin "P$1") (pinfunction "SPARE4_P$1") (pintype "bidirectional"))
    )
    (net (code "30") (name "SPARE5") (class "Default")
      (node (ref "U$1") (pin "35") (pinfunction "SPARE5_35") (pintype "bidirectional"))
      (node (ref "U$2") (pin "35") (pinfunction "SPARE5_35") (pintype "bidirectional"))
      (node (ref "U$3") (pin "35") (pinfunction "SPARE5_35") (pintype "bidirectional"))
      (node (ref "U$5") (pin "P$9") (pinfunction "SPARE5_P$9") (pintype "bidirectional"))
    )
    (net (code "31") (name "SPARE6") (class "Default")
      (node (ref "U$1") (pin "36") (pinfunction "SPARE6_36") (pintype "bidirectional"))
      (node (ref "U$2") (pin "36") (pinfunction "SPARE6_36") (pintype "bidirectional"))
      (node (ref "U$3") (pin "36") (pinfunction "SPARE6_36") (pintype "bidirectional"))
      (node (ref "U$5") (pin "P$8") (pinfunction "SPARE6_P$8") (pintype "bidirectional"))
    )
    (net (code "32") (name "SPARE7") (class "Default")
      (node (ref "U$1") (pin "43") (pinfunction "SPARE7_43") (pintype "bidirectional"))
      (node (ref "U$2") (pin "43") (pinfunction "SPARE7_43") (pintype "bidirectional"))
      (node (ref "U$3") (pin "43") (pinfunction "SPARE7_43") (pintype "bidirectional"))
      (node (ref "U$5") (pin "P$1") (pinfunction "SPARE7_P$1") (pintype "bidirectional"))
    )
    (net (code "33") (name "SWITCH_1") (class "Default")
      (node (ref "R10") (pin "2") (pinfunction "2_2") (pintype "passive"))
      (node (ref "SWITCH_CONNECTOR") (pin "3") (pinfunction "P_3") (pintype "passive"))
      (node (ref "U$1") (pin "38") (pinfunction "SWITCH_1_38") (pintype "output"))
      (node (ref "U$2") (pin "38") (pinfunction "SWITCH_1_38") (pintype "output"))
      (node (ref "U$3") (pin "38") (pinfunction "SWITCH_1_38") (pintype "output"))
      (node (ref "U$5") (pin "P$6") (pinfunction "SWITCH_1_P$6") (pintype "bidirectional"))
    )
    (net (code "34") (name "SWITCH_2") (class "Default")
      (node (ref "R11") (pin "2") (pinfunction "2_2") (pintype "passive"))
      (node (ref "SWITCH_CONNECTOR") (pin "4") (pinfunction "P_4") (pintype "passive"))
      (node (ref "U$1") (pin "39") (pinfunction "SWITCH_2_39") (pintype "output"))
      (node (ref "U$2") (pin "39") (pinfunction "SWITCH_2_39") (pintype "output"))
      (node (ref "U$3") (pin "39") (pinfunction "SWITCH_2_39") (pintype "output"))
      (node (ref "U$5") (pin "P$5") (pinfunction "SWITCH_2_P$5") (pintype "bidirectional"))
    )
    (net (code "35") (name "SWITCH_3") (class "Default")
      (node (ref "R12") (pin "2") (pinfunction "2_2") (pintype "passive"))
      (node (ref "SWITCH_CONNECTOR") (pin "6") (pinfunction "P_6") (pintype "passive"))
      (node (ref "U$1") (pin "40") (pinfunction "SWITCH_3_40") (pintype "output"))
      (node (ref "U$2") (pin "40") (pinfunction "SWITCH_3_40") (pintype "output"))
      (node (ref "U$3") (pin "40") (pinfunction "SWITCH_3_40") (pintype "output"))
      (node (ref "U$5") (pin "P$4") (pinfunction "SWITCH_3_P$4") (pintype "bidirectional"))
    )
    (net (code "36") (name "SWITCH_4") (class "Default")
      (node (ref "R13") (pin "2") (pinfunction "2_2") (pintype "passive"))
      (node (ref "SWITCH_CONNECTOR") (pin "7") (pinfunction "P_7") (pintype "passive"))
      (node (ref "U$1") (pin "41") (pinfunction "SWITCH_4_41") (pintype "output"))
      (node (ref "U$2") (pin "41") (pinfunction "SWITCH_4_41") (pintype "output"))
      (node (ref "U$3") (pin "41") (pinfunction "SWITCH_4_41") (pintype "output"))
      (node (ref "U$5") (pin "P$3") (pinfunction "SWITCH_4_P$3") (pintype "bidirectional"))
    )
    (net (code "37") (name "SWITCH_5") (class "Default")
      (node (ref "R14") (pin "2") (pinfunction "2_2") (pintype "passive"))
      (node (ref "SWITCH_CONNECTOR") (pin "8") (pinfunction "P_8") (pintype "passive"))
      (node (ref "U$1") (pin "42") (pinfunction "SWITCH_5_42") (pintype "output"))
      (node (ref "U$2") (pin "42") (pinfunction "SWITCH_5_42") (pintype "output"))
      (node (ref "U$3") (pin "42") (pinfunction "SWITCH_5_42") (pintype "output"))
      (node (ref "U$5") (pin "P$2") (pinfunction "SWITCH_5_P$2") (pintype "bidirectional"))
    )
    (net (code "38") (name "unconnected-(U$4-BOOT0-Pad60)") (class "Default")
      (node (ref "U$4") (pin "60") (pinfunction "BOOT0_60") (pintype "bidirectional"))
    )
    (net (code "39") (name "unconnected-(U$4-NRST-Pad7)") (class "Default")
      (node (ref "U$4") (pin "7") (pinfunction "NRST_7") (pintype "bidirectional"))
    )
    (net (code "40") (name "unconnected-(U$4-PA0-Pad14)") (class "Default")
      (node (ref "U$4") (pin "14") (pinfunction "PA0_14") (pintype "bidirectional"))
    )
    (net (code "41") (name "unconnected-(U$4-PA1-Pad15)") (class "Default")
      (node (ref "U$4") (pin "15") (pinfunction "PA1_15") (pintype "bidirectional"))
    )
    (net (code "42") (name "unconnected-(U$4-PA2{slash}UART2_TX-Pad16)") (class "Default")
      (node (ref "U$4") (pin "16") (pinfunction "PA2/UART2_TX_16") (pintype "bidirectional"))
    )
    (net (code "43") (name "unconnected-(U$4-PA3{slash}UART2_RX-Pad17)") (class "Default")
      (node (ref "U$4") (pin "17") (pinfunction "PA3/UART2_RX_17") (pintype "bidirectional"))
    )
    (net (code "44") (name "unconnected-(U$4-PA4{slash}SPI1_NSS-Pad20)") (class "Default")
      (node (ref "U$4") (pin "20") (pinfunction "PA4/SPI1_NSS_20") (pintype "bidirectional"))
    )
    (net (code "45") (name "unconnected-(U$4-PA5{slash}SPI1_SCK-Pad21)") (class "Default")
      (node (ref "U$4") (pin "21") (pinfunction "PA5/SPI1_SCK_21") (pintype "bidirectional"))
    )
    (net (code "46") (name "unconnected-(U$4-PA6{slash}SPI1_MISO-Pad22)") (class "Default")
      (node (ref "U$4") (pin "22") (pinfunction "PA6/SPI1_MISO_22") (pintype "bidirectional"))
    )
    (net (code "47") (name "unconnected-(U$4-PA7{slash}SPI1_MOSI-Pad23)") (class "Default")
      (node (ref "U$4") (pin "23") (pinfunction "PA7/SPI1_MOSI_23") (pintype "bidirectional"))
    )
    (net (code "48") (name "unconnected-(U$4-PA8-Pad41)") (class "Default")
      (node (ref "U$4") (pin "41") (pinfunction "PA8_41") (pintype "bidirectional"))
    )
    (net (code "49") (name "unconnected-(U$4-PA9{slash}UART1_TX-Pad42)") (class "Default")
      (node (ref "U$4") (pin "42") (pinfunction "PA9/UART1_TX_42") (pintype "bidirectional"))
    )
    (net (code "50") (name "unconnected-(U$4-PA10{slash}UART1_RX-Pad43)") (class "Default")
      (node (ref "U$4") (pin "43") (pinfunction "PA10/UART1_RX_43") (pintype "bidirectional"))
    )
    (net (code "51") (name "unconnected-(U$4-PA11-Pad44)") (class "Default")
      (node (ref "U$4") (pin "44") (pinfunction "PA11_44") (pintype "bidirectional"))
    )
    (net (code "52") (name "unconnected-(U$4-PA12-Pad45)") (class "Default")
      (node (ref "U$4") (pin "45") (pinfunction "PA12_45") (pintype "bidirectional"))
    )
    (net (code "53") (name "unconnected-(U$4-PA13{slash}JTMS-Pad46)") (class "Default")
      (node (ref "U$4") (pin "46") (pinfunction "PA13/JTMS_46") (pintype "bidirectional"))
    )
    (net (code "54") (name "unconnected-(U$4-PA14{slash}JTCK-Pad49)") (class "Default")
      (node (ref "U$4") (pin "49") (pinfunction "PA14/JTCK_49") (pintype "bidirectional"))
    )
    (net (code "55") (name "unconnected-(U$4-PA15{slash}JTDI-Pad50)") (class "Default")
      (node (ref "U$4") (pin "50") (pinfunction "PA15/JTDI_50") (pintype "bidirectional"))
    )
    (net (code "56") (name "unconnected-(U$4-PB0-Pad26)") (class "Default")
      (node (ref "U$4") (pin "26") (pinfunction "PB0_26") (pintype "bidirectional"))
    )
    (net (code "57") (name "unconnected-(U$4-PB1-Pad27)") (class "Default")
      (node (ref "U$4") (pin "27") (pinfunction "PB1_27") (pintype "bidirectional"))
    )
    (net (code "58") (name "unconnected-(U$4-PB2-BOOT1-Pad28)") (class "Default")
      (node (ref "U$4") (pin "28") (pinfunction "PB2-BOOT1_28") (pintype "bidirectional"))
    )
    (net (code "59") (name "unconnected-(U$4-PB3{slash}JTDO-Pad55)") (class "Default")
      (node (ref "U$4") (pin "55") (pinfunction "PB3/JTDO_55") (pintype "bidirectional"))
    )
    (net (code "60") (name "unconnected-(U$4-PB4{slash}JTRST-Pad56)") (class "Default")
      (node (ref "U$4") (pin "56") (pinfunction "PB4/JTRST_56") (pintype "bidirectional"))
    )
    (net (code "61") (name "unconnected-(U$4-PB5-Pad57)") (class "Default")
      (node (ref "U$4") (pin "57") (pinfunction "PB5_57") (pintype "bidirectional"))
    )
    (net (code "62") (name "unconnected-(U$4-PB6-Pad58)") (class "Default")
      (node (ref "U$4") (pin "58") (pinfunction "PB6_58") (pintype "bidirectional"))
    )
    (net (code "63") (name "unconnected-(U$4-PB7-Pad59)") (class "Default")
      (node (ref "U$4") (pin "59") (pinfunction "PB7_59") (pintype "bidirectional"))
    )
    (net (code "64") (name "unconnected-(U$4-PB8-Pad61)") (class "Default")
      (node (ref "U$4") (pin "61") (pinfunction "PB8_61") (pintype "bidirectional"))
    )
    (net (code "65") (name "unconnected-(U$4-PB9-Pad62)") (class "Default")
      (node (ref "U$4") (pin "62") (pinfunction "PB9_62") (pintype "bidirectional"))
    )
    (net (code "66") (name "unconnected-(U$4-PB10-Pad29)") (class "Default")
      (node (ref "U$4") (pin "29") (pinfunction "PB10_29") (pintype "bidirectional"))
    )
    (net (code "67") (name "unconnected-(U$4-PB11-Pad30)") (class "Default")
      (node (ref "U$4") (pin "30") (pinfunction "PB11_30") (pintype "bidirectional"))
    )
    (net (code "68") (name "unconnected-(U$4-PB12{slash}I2S2_WS-Pad33)") (class "Default")
      (node (ref "U$4") (pin "33") (pinfunction "PB12/I2S2_WS_33") (pintype "bidirectional"))
    )
    (net (code "69") (name "unconnected-(U$4-PB13{slash}I2S2_CK-Pad34)") (class "Default")
      (node (ref "U$4") (pin "34") (pinfunction "PB13/I2S2_CK_34") (pintype "bidirectional"))
    )
    (net (code "70") (name "unconnected-(U$4-PB14{slash}I2S2_XD-Pad35)") (class "Default")
      (node (ref "U$4") (pin "35") (pinfunction "PB14/I2S2_XD_35") (pintype "bidirectional"))
    )
    (net (code "71") (name "unconnected-(U$4-PB15{slash}I2S2_SD-Pad36)") (class "Default")
      (node (ref "U$4") (pin "36") (pinfunction "PB15/I2S2_SD_36") (pintype "bidirectional"))
    )
    (net (code "72") (name "unconnected-(U$4-PC0-Pad8)") (class "Default")
      (node (ref "U$4") (pin "8") (pinfunction "PC0_8") (pintype "bidirectional"))
    )
    (net (code "73") (name "unconnected-(U$4-PC1-Pad9)") (class "Default")
      (node (ref "U$4") (pin "9") (pinfunction "PC1_9") (pintype "bidirectional"))
    )
    (net (code "74") (name "unconnected-(U$4-PC2-Pad10)") (class "Default")
      (node (ref "U$4") (pin "10") (pinfunction "PC2_10") (pintype "bidirectional"))
    )
    (net (code "75") (name "unconnected-(U$4-PC3-Pad11)") (class "Default")
      (node (ref "U$4") (pin "11") (pinfunction "PC3_11") (pintype "bidirectional"))
    )
    (net (code "76") (name "unconnected-(U$4-PC4-Pad24)") (class "Default")
      (node (ref "U$4") (pin "24") (pinfunction "PC4_24") (pintype "bidirectional"))
    )
    (net (code "77") (name "unconnected-(U$4-PC5-Pad25)") (class "Default")
      (node (ref "U$4") (pin "25") (pinfunction "PC5_25") (pintype "bidirectional"))
    )
    (net (code "78") (name "unconnected-(U$4-PC6{slash}I2S2_MCK-Pad37)") (class "Default")
      (node (ref "U$4") (pin "37") (pinfunction "PC6/I2S2_MCK_37") (pintype "bidirectional"))
    )
    (net (code "79") (name "unconnected-(U$4-PC7-Pad38)") (class "Default")
      (node (ref "U$4") (pin "38") (pinfunction "PC7_38") (pintype "bidirectional"))
    )
    (net (code "80") (name "unconnected-(U$4-PC8{slash}SDIO_D0-Pad39)") (class "Default")
      (node (ref "U$4") (pin "39") (pinfunction "PC8/SDIO_D0_39") (pintype "bidirectional"))
    )
    (net (code "81") (name "unconnected-(U$4-PC9{slash}SDIO_D1-Pad40)") (class "Default")
      (node (ref "U$4") (pin "40") (pinfunction "PC9/SDIO_D1_40") (pintype "bidirectional"))
    )
    (net (code "82") (name "unconnected-(U$4-PC10{slash}SDIO_D2-Pad51)") (class "Default")
      (node (ref "U$4") (pin "51") (pinfunction "PC10/SDIO_D2_51") (pintype "bidirectional"))
    )
    (net (code "83") (name "unconnected-(U$4-PC11{slash}SDIO_D3-Pad52)") (class "Default")
      (node (ref "U$4") (pin "52") (pinfunction "PC11/SDIO_D3_52") (pintype "bidirectional"))
    )
    (net (code "84") (name "unconnected-(U$4-PC12{slash}SDIO_CLK-Pad53)") (class "Default")
      (node (ref "U$4") (pin "53") (pinfunction "PC12/SDIO_CLK_53") (pintype "bidirectional"))
    )
    (net (code "85") (name "unconnected-(U$4-PC13-Pad2)") (class "Default")
      (node (ref "U$4") (pin "2") (pinfunction "PC13_2") (pintype "bidirectional"))
    )
    (net (code "86") (name "unconnected-(U$4-PC14-Pad3)") (class "Default")
      (node (ref "U$4") (pin "3") (pinfunction "PC14_3") (pintype "bidirectional"))
    )
    (net (code "87") (name "unconnected-(U$4-PC15-Pad4)") (class "Default")
      (node (ref "U$4") (pin "4") (pinfunction "PC15_4") (pintype "bidirectional"))
    )
    (net (code "88") (name "unconnected-(U$4-PD2{slash}SDIO_CMD-Pad54)") (class "Default")
      (node (ref "U$4") (pin "54") (pinfunction "PD2/SDIO_CMD_54") (pintype "bidirectional"))
    )
    (net (code "89") (name "unconnected-(U$4-PH0-Pad5)") (class "Default")
      (node (ref "U$4") (pin "5") (pinfunction "PH0_5") (pintype "bidirectional"))
    )
    (net (code "90") (name "unconnected-(U$4-PH1-Pad6)") (class "Default")
      (node (ref "U$4") (pin "6") (pinfunction "PH1_6") (pintype "bidirectional"))
    )
    (net (code "91") (name "unconnected-(U$4-VBAT-Pad1)") (class "Default")
      (node (ref "U$4") (pin "1") (pinfunction "VBAT_1") (pintype "bidirectional"))
    )
  )
)
